# lab.net
KiCad netlist of a schematic drawn in EAGLE
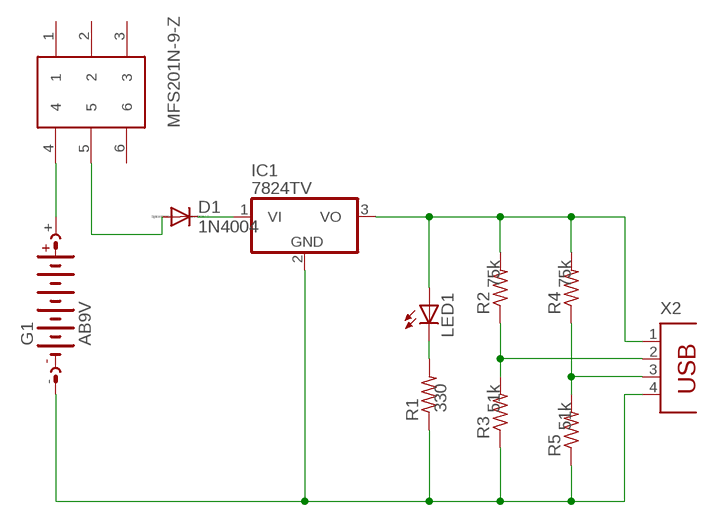
[diagram p0: schematic, sheet 1]

(export (version "E")
  (design (tool "Eeschema 10.0.6"))
  (components
    (comp (ref "D1")
      (value "1N4004")
      (footprint "eagle-import:DO41-10")
      (libsource (lib "eagle-import") (part "1N4004"))
    )
    (comp (ref "G1")
      (value "AB9V")
      (footprint "eagle-import:AB9V")
      (libsource (lib "eagle-import") (part "AB9V"))
    )
    (comp (ref "IC1")
      (value "7824TV")
      (footprint "eagle-import:TO220V")
      (libsource (lib "eagle-import") (part "78TV24"))
    )
    (comp (ref "LED1")
      (value "LED5MM")
      (footprint "eagle-import:LED5MM")
      (libsource (lib "eagle-import") (part "LED5MM"))
    )
    (comp (ref "R1")
      (value "R-US_0207/10")
      (footprint "eagle-import:0207_10")
      (fields (field (name "SPICEPREFIX") "R") (field (name "SPICEPREFIX_1") "330"))
      (libsource (lib "eagle-import") (part "R-US_0207/10"))
    )
    (comp (ref "R2")
      (value "R-US_0207/10")
      (footprint "eagle-import:0207_10")
      (fields (field (name "SPICEPREFIX") "R") (field (name "SPICEPREFIX_1") "75k"))
      (libsource (lib "eagle-import") (part "R-US_0207/10"))
    )
    (comp (ref "R3")
      (value "R-US_0207/10")
      (footprint "eagle-import:0207_10")
      (fields (field (name "SPICEPREFIX") "R") (field (name "SPICEPREFIX_1") "51k"))
      (libsource (lib "eagle-import") (part "R-US_0207/10"))
    )
    (comp (ref "R4")
      (value "R-US_0207/10")
      (footprint "eagle-import:0207_10")
      (fields (field (name "SPICEPREFIX") "R") (field (name "SPICEPREFIX_1") "75k"))
      (libsource (lib "eagle-import") (part "R-US_0207/10"))
    )
    (comp (ref "R5")
      (value "R-US_0207/10")
      (footprint "eagle-import:0207_10")
      (fields (field (name "SPICEPREFIX") "R") (field (name "SPICEPREFIX_1") "51k"))
      (libsource (lib "eagle-import") (part "R-US_0207/10"))
    )
    (comp (ref "U$1")
      (value "MFS201N-9-Z")
      (footprint "eagle-import:MFS201N-9-Z")
      (libsource (lib "eagle-import") (part "MFS201N-9-Z"))
    )
    (comp (ref "X2")
      (value "PN87520")
      (footprint "eagle-import:PN87520")
      (libsource (lib "eagle-import") (part "PN87520"))
    )
  )
  (nets
    (net (code "1") (name "Net-(D1-PadA)") (class "Default")
      (node (ref "D1") (pin "A") (pinfunction "A_A") (pintype "passive"))
      (node (ref "U$1") (pin "5") (pinfunction "5_5") (pintype "bidirectional"))
    )
    (net (code "2") (name "Net-(G1-Pad+)") (class "Default")
      (node (ref "G1") (pin "+") (pinfunction "+_+") (pintype "passive"))
      (node (ref "U$1") (pin "4") (pinfunction "4_4") (pintype "bidirectional"))
    )
    (net (code "3") (name "Net-(IC1-GND)") (class "Default")
      (node (ref "G1") (pin "-") (pinfunction "-_-") (pintype "passive"))
      (node (ref "IC1") (pin "2") (pinfunction "GND_2") (pintype "passive"))
      (node (ref "R1") (pin "1") (pinfunction "1_1") (pintype "passive"))
      (node (ref "R3") (pin "1") (pinfunction "1_1") (pintype "passive"))
      (node (ref "R5") (pin "1") (pinfunction "1_1") (pintype "passive"))
      (node (ref "X2") (pin "4") (pinfunction "4_4") (pintype "passive"))
    )
    (net (code "4") (name "Net-(IC1-VI)") (class "Default")
      (node (ref "D1") (pin "C") (pinfunction "C_C") (pintype "passive"))
      (node (ref "IC1") (pin "1") (pinfunction "VI_1") (pintype "input"))
    )
    (net (code "5") (name "Net-(IC1-VO)") (class "Default")
      (node (ref "IC1") (pin "3") (pinfunction "VO_3") (pintype "passive"))
      (node (ref "LED1") (pin "A") (pinfunction "A_A") (pintype "passive"))
      (node (ref "R2") (pin "2") (pinfunction "2_2") (pintype "passive"))
      (node (ref "R4") (pin "2") (pinfunction "2_2") (pintype "passive"))
      (node (ref "X2") (pin "1") (pinfunction "1_1") (pintype "passive"))
    )
    (net (code "6") (name "Net-(LED1-C)") (class "Default")
      (node (ref "LED1") (pin "K") (pinfunction "C_K") (pintype "passive"))
      (node (ref "R1") (pin "2") (pinfunction "2_2") (pintype "passive"))
    )
    (net (code "7") (name "Net-(R2-Pad1)") (class "Default")
      (node (ref "R2") (pin "1") (pinfunction "1_1") (pintype "passive"))
      (node (ref "R3") (pin "2") (pinfunction "2_2") (pintype "passive"))
      (node (ref "X2") (pin "2") (pinfunction "2_2") (pintype "passive"))
    )
    (net (code "8") (name "Net-(R4-Pad1)") (class "Default")
      (node (ref "R4") (pin "1") (pinfunction "1_1") (pintype "passive"))
      (node (ref "R5") (pin "2") (pinfunction "2_2") (pintype "passive"))
      (node (ref "X2") (pin "3") (pinfunction "3_3") (pintype "passive"))
    )
    (net (code "9") (name "unconnected-(U$1-Pad1)") (class "Default")
      (node (ref "U$1") (pin "1") (pinfunction "1_1") (pintype "bidirectional"))
    )
    (net (code "10") (name "unconnected-(U$1-Pad2)") (class "Default")
      (node (ref "U$1") (pin "2") (pinfunction "2_2") (pintype "bidirectional"))
    )
    (net (code "11") (name "unconnected-(U$1-Pad3)") (class "Default")
      (node (ref "U$1") (pin "3") (pinfunction "3_3") (pintype "bidirectional"))
    )
    (net (code "12") (name "unconnected-(U$1-Pad6)") (class "Default")
      (node (ref "U$1") (pin "6") (pinfunction "6_6") (pintype "bidirectional"))
    )
  )
)
